# 1541-II_multi-ROM_Rev2.net
KiCad netlist of a schematic drawn in EAGLE
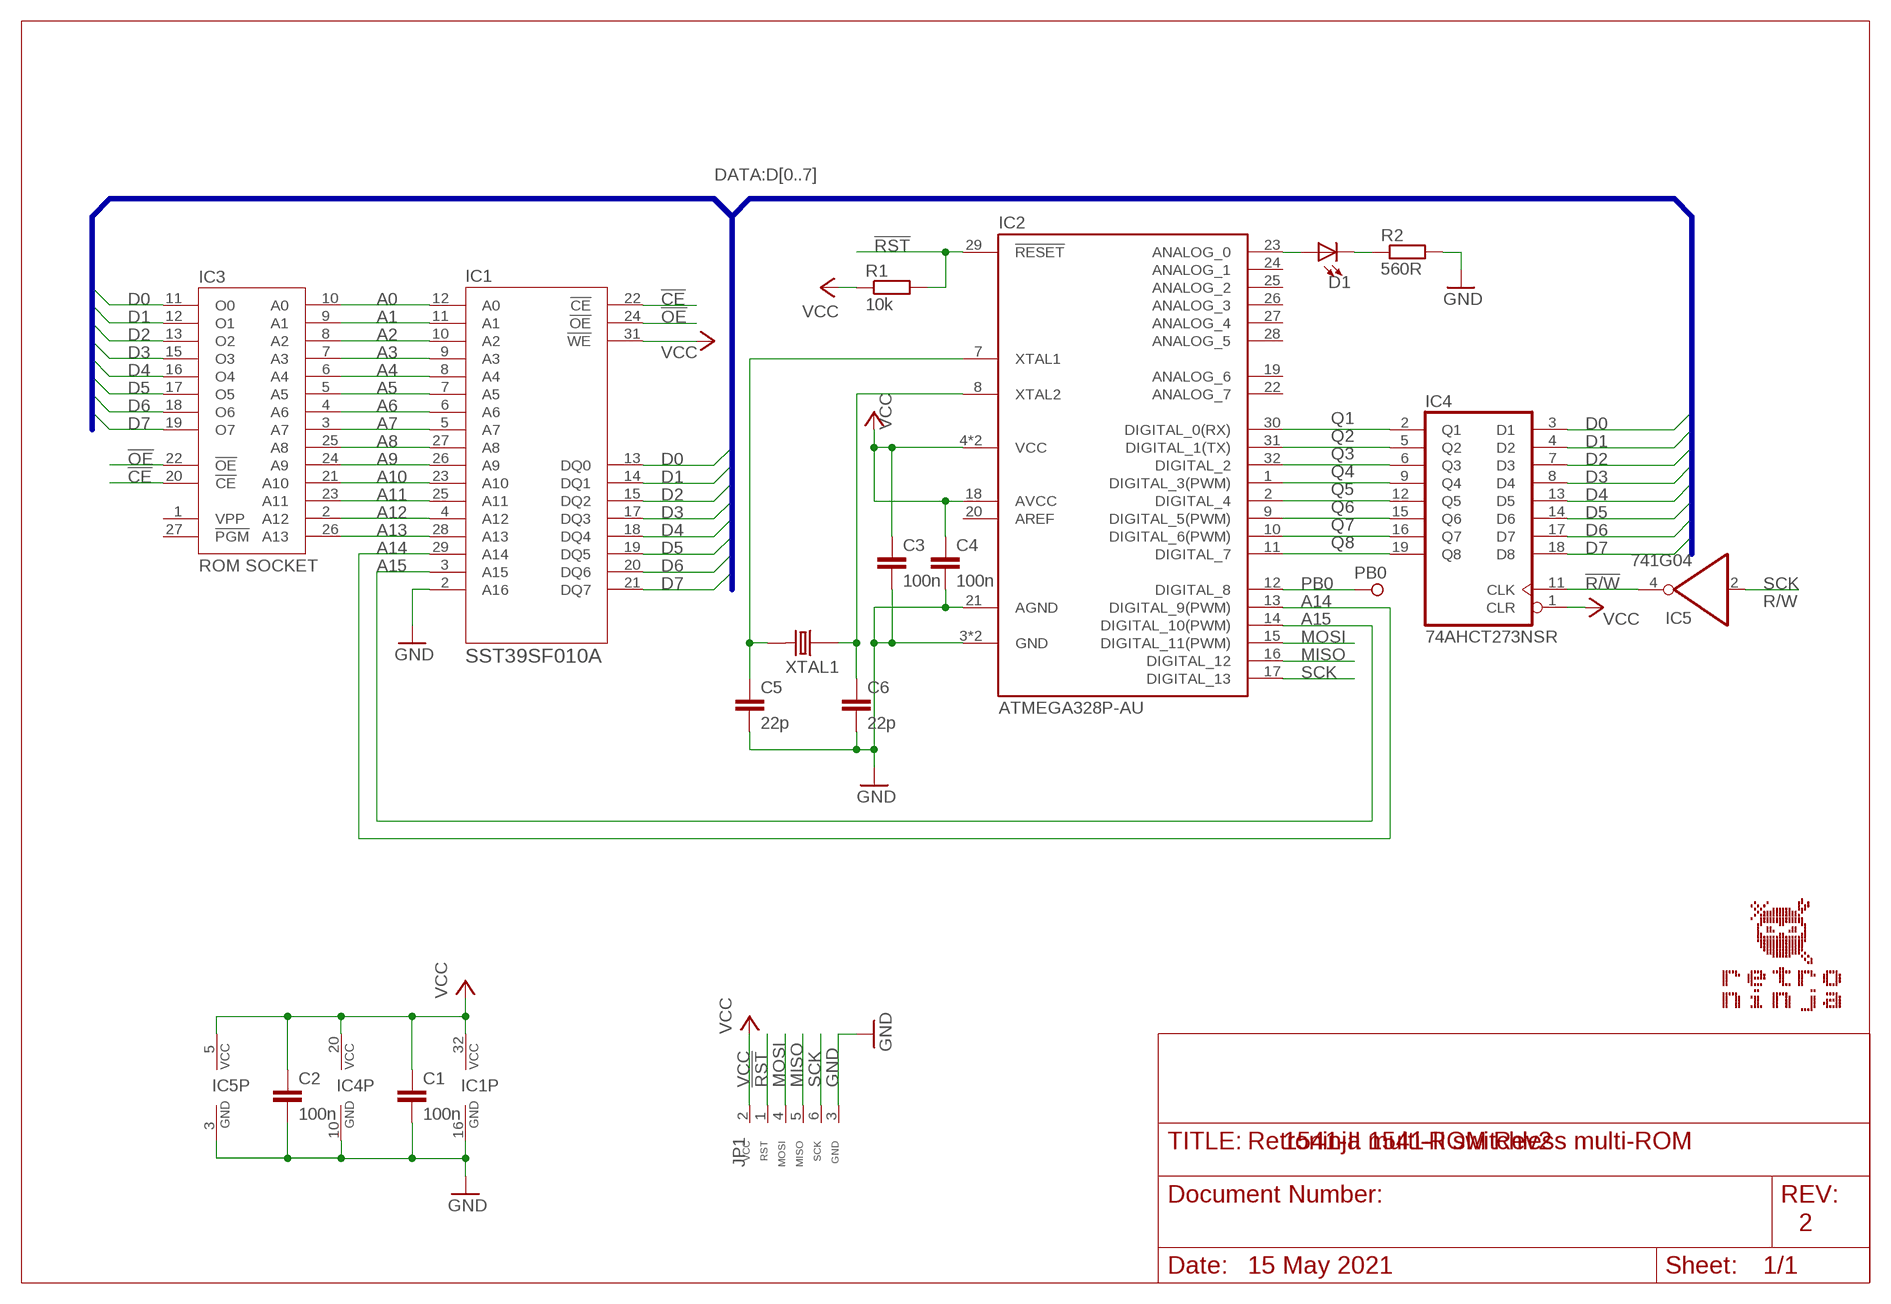
[diagram p0: schematic, sheet 1]

(export (version "E")
  (design (tool "Eeschema 10.0.6"))
  (components
    (comp (ref "C1")
      (value "100n")
      (footprint "eagle-import:C0805")
      (libsource (lib "eagle-import") (part "C-EUC0805"))
    )
    (comp (ref "C2")
      (value "100n")
      (footprint "eagle-import:C0805")
      (libsource (lib "eagle-import") (part "C-EUC0805"))
    )
    (comp (ref "C3")
      (value "100n")
      (footprint "eagle-import:C0805")
      (libsource (lib "eagle-import") (part "C-EUC0805"))
    )
    (comp (ref "C4")
      (value "100n")
      (footprint "eagle-import:C0805")
      (libsource (lib "eagle-import") (part "C-EUC0805"))
    )
    (comp (ref "C5")
      (value "22p")
      (footprint "eagle-import:C0805")
      (libsource (lib "eagle-import") (part "C-EUC0805"))
    )
    (comp (ref "C6")
      (value "22p")
      (footprint "eagle-import:C0805")
      (libsource (lib "eagle-import") (part "C-EUC0805"))
    )
    (comp (ref "D1")
      (value "LED_1206")
      (footprint "eagle-import:LED1206")
      (libsource (lib "eagle-import") (part "LED_1206"))
    )
    (comp (ref "IC1")
      (value "SST39SF010A")
      (footprint "eagle-import:PLCC32_SHORT")
      (libsource (lib "eagle-import") (part "SST39XX010_PLCC_SHORT"))
    )
    (comp (ref "IC2")
      (value "ATMEGA328P-AU")
      (footprint "eagle-import:TQFP32")
      (libsource (lib "eagle-import") (part "ARDUINO_168_328_TQFP"))
    )
    (comp (ref "IC3")
      (value "ROM SOCKET")
      (footprint "eagle-import:DIL28-6_DOWNPINS")
      (libsource (lib "eagle-import") (part "27C128_DOWNPINS"))
    )
    (comp (ref "IC4")
      (value "74AHCT273NSR")
      (footprint "eagle-import:SO20")
      (libsource (lib "eagle-import") (part "74273NS"))
    )
    (comp (ref "IC5")
      (value "741G04")
      (footprint "eagle-import:SOT23-5")
      (libsource (lib "eagle-import") (part "741G04_SOT23"))
    )
    (comp (ref "JP1")
      (value "ICSP_CONNECTOR_TL866_RIGHT2")
      (footprint "eagle-import:HEADER_1X6_RIGHT")
      (libsource (lib "eagle-import") (part "ICSP_CONNECTOR_TL866_RIGHT2"))
    )
    (comp (ref "PB0")
      (value "TEST_POINT_TH")
      (footprint "eagle-import:TEST_POINT_TH")
      (libsource (lib "eagle-import") (part "TEST_POINT_TH"))
    )
    (comp (ref "R1")
      (value "10k")
      (footprint "eagle-import:R0805")
      (libsource (lib "eagle-import") (part "R-EU_R0805"))
    )
    (comp (ref "R2")
      (value "560R")
      (footprint "eagle-import:R0805")
      (libsource (lib "eagle-import") (part "R-EU_R0805"))
    )
    (comp (ref "XTAL1")
      (value "CRYSTAL")
      (footprint "eagle-import:CRYSTAL_SMD-2_7X4X2.3")
      (libsource (lib "eagle-import") (part "CRYSTAL"))
    )
  )
  (nets
    (net (code "9") (name "/A0") (class "Default")
      (node (ref "IC1") (pin "12") (pinfunction "A0_12") (pintype "input"))
      (node (ref "IC3") (pin "10") (pinfunction "A0_10") (pintype "input"))
    )
    (net (code "10") (name "/A1") (class "Default")
      (node (ref "IC1") (pin "11") (pinfunction "A1_11") (pintype "input"))
      (node (ref "IC3") (pin "9") (pinfunction "A1_9") (pintype "input"))
    )
    (net (code "11") (name "/A2") (class "Default")
      (node (ref "IC1") (pin "10") (pinfunction "A2_10") (pintype "input"))
      (node (ref "IC3") (pin "8") (pinfunction "A2_8") (pintype "input"))
    )
    (net (code "12") (name "/A3") (class "Default")
      (node (ref "IC1") (pin "9") (pinfunction "A3_9") (pintype "input"))
      (node (ref "IC3") (pin "7") (pinfunction "A3_7") (pintype "input"))
    )
    (net (code "13") (name "/A4") (class "Default")
      (node (ref "IC1") (pin "8") (pinfunction "A4_8") (pintype "input"))
      (node (ref "IC3") (pin "6") (pinfunction "A4_6") (pintype "input"))
    )
    (net (code "14") (name "/A5") (class "Default")
      (node (ref "IC1") (pin "7") (pinfunction "A5_7") (pintype "input"))
      (node (ref "IC3") (pin "5") (pinfunction "A5_5") (pintype "input"))
    )
    (net (code "15") (name "/A6") (class "Default")
      (node (ref "IC1") (pin "6") (pinfunction "A6_6") (pintype "input"))
      (node (ref "IC3") (pin "4") (pinfunction "A6_4") (pintype "input"))
    )
    (net (code "16") (name "/A7") (class "Default")
      (node (ref "IC1") (pin "5") (pinfunction "A7_5") (pintype "input"))
      (node (ref "IC3") (pin "3") (pinfunction "A7_3") (pintype "input"))
    )
    (net (code "17") (name "/A8") (class "Default")
      (node (ref "IC1") (pin "27") (pinfunction "A8_27") (pintype "input"))
      (node (ref "IC3") (pin "25") (pinfunction "A8_25") (pintype "input"))
    )
    (net (code "18") (name "/A9") (class "Default")
      (node (ref "IC1") (pin "26") (pinfunction "A9_26") (pintype "input"))
      (node (ref "IC3") (pin "24") (pinfunction "A9_24") (pintype "input"))
    )
    (net (code "19") (name "/A10") (class "Default")
      (node (ref "IC1") (pin "23") (pinfunction "A10_23") (pintype "input"))
      (node (ref "IC3") (pin "21") (pinfunction "A10_21") (pintype "input"))
    )
    (net (code "20") (name "/A11") (class "Default")
      (node (ref "IC1") (pin "25") (pinfunction "A11_25") (pintype "input"))
      (node (ref "IC3") (pin "23") (pinfunction "A11_23") (pintype "input"))
    )
    (net (code "21") (name "/A12") (class "Default")
      (node (ref "IC1") (pin "4") (pinfunction "A12_4") (pintype "input"))
      (node (ref "IC3") (pin "2") (pinfunction "A12_2") (pintype "input"))
    )
    (net (code "22") (name "/A13") (class "Default")
      (node (ref "IC1") (pin "28") (pinfunction "A13_28") (pintype "input"))
      (node (ref "IC3") (pin "26") (pinfunction "A13_26") (pintype "input"))
    )
    (net (code "23") (name "/A14") (class "Default")
      (node (ref "IC1") (pin "29") (pinfunction "A14_29") (pintype "input"))
      (node (ref "IC2") (pin "13") (pinfunction "DIGITAL_9(PWM)_13") (pintype "bidirectional"))
    )
    (net (code "24") (name "/A15") (class "Default")
      (node (ref "IC1") (pin "3") (pinfunction "A15_3") (pintype "input"))
      (node (ref "IC2") (pin "14") (pinfunction "DIGITAL_10(PWM)_14") (pintype "bidirectional"))
    )
    (net (code "25") (name "/D0") (class "Default")
      (node (ref "IC1") (pin "13") (pinfunction "DQ0_13") (pintype "bidirectional"))
      (node (ref "IC3") (pin "11") (pinfunction "O0_11") (pintype "tri_state"))
      (node (ref "IC4") (pin "3") (pinfunction "D1_3") (pintype "input"))
    )
    (net (code "26") (name "/D1") (class "Default")
      (node (ref "IC1") (pin "14") (pinfunction "DQ1_14") (pintype "bidirectional"))
      (node (ref "IC3") (pin "12") (pinfunction "O1_12") (pintype "tri_state"))
      (node (ref "IC4") (pin "4") (pinfunction "D2_4") (pintype "input"))
    )
    (net (code "27") (name "/D2") (class "Default")
      (node (ref "IC1") (pin "15") (pinfunction "DQ2_15") (pintype "bidirectional"))
      (node (ref "IC3") (pin "13") (pinfunction "O2_13") (pintype "tri_state"))
      (node (ref "IC4") (pin "7") (pinfunction "D3_7") (pintype "input"))
    )
    (net (code "28") (name "/D3") (class "Default")
      (node (ref "IC1") (pin "17") (pinfunction "DQ3_17") (pintype "bidirectional"))
      (node (ref "IC3") (pin "15") (pinfunction "O3_15") (pintype "tri_state"))
      (node (ref "IC4") (pin "8") (pinfunction "D4_8") (pintype "input"))
    )
    (net (code "29") (name "/D4") (class "Default")
      (node (ref "IC1") (pin "18") (pinfunction "DQ4_18") (pintype "bidirectional"))
      (node (ref "IC3") (pin "16") (pinfunction "O4_16") (pintype "tri_state"))
      (node (ref "IC4") (pin "13") (pinfunction "D5_13") (pintype "input"))
    )
    (net (code "30") (name "/D5") (class "Default")
      (node (ref "IC1") (pin "19") (pinfunction "DQ5_19") (pintype "bidirectional"))
      (node (ref "IC3") (pin "17") (pinfunction "O5_17") (pintype "tri_state"))
      (node (ref "IC4") (pin "14") (pinfunction "D6_14") (pintype "input"))
    )
    (net (code "31") (name "/D6") (class "Default")
      (node (ref "IC1") (pin "20") (pinfunction "DQ6_20") (pintype "bidirectional"))
      (node (ref "IC3") (pin "18") (pinfunction "O6_18") (pintype "tri_state"))
      (node (ref "IC4") (pin "17") (pinfunction "D7_17") (pintype "input"))
    )
    (net (code "32") (name "/D7") (class "Default")
      (node (ref "IC1") (pin "21") (pinfunction "DQ7_21") (pintype "bidirectional"))
      (node (ref "IC3") (pin "19") (pinfunction "O7_19") (pintype "tri_state"))
      (node (ref "IC4") (pin "18") (pinfunction "D8_18") (pintype "input"))
    )
    (net (code "34") (name "/MISO") (class "Default")
      (node (ref "IC2") (pin "16") (pinfunction "DIGITAL_12_16") (pintype "bidirectional"))
      (node (ref "JP1") (pin "5") (pinfunction "MISO_5") (pintype "output"))
    )
    (net (code "35") (name "/MOSI") (class "Default")
      (node (ref "IC2") (pin "15") (pinfunction "DIGITAL_11(PWM)_15") (pintype "bidirectional"))
      (node (ref "JP1") (pin "4") (pinfunction "MOSI_4") (pintype "input"))
    )
    (net (code "36") (name "/PB0") (class "Default")
      (node (ref "IC2") (pin "12") (pinfunction "DIGITAL_8_12") (pintype "bidirectional"))
      (node (ref "PB0") (pin "P$1") (pinfunction "TP_P$1") (pintype "passive"))
    )
    (net (code "37") (name "/Q1") (class "Default")
      (node (ref "IC2") (pin "30") (pinfunction "DIGITAL_0(RX)_30") (pintype "bidirectional"))
      (node (ref "IC4") (pin "2") (pinfunction "Q1_2") (pintype "output"))
    )
    (net (code "38") (name "/Q2") (class "Default")
      (node (ref "IC2") (pin "31") (pinfunction "DIGITAL_1(TX)_31") (pintype "bidirectional"))
      (node (ref "IC4") (pin "5") (pinfunction "Q2_5") (pintype "output"))
    )
    (net (code "39") (name "/Q3") (class "Default")
      (node (ref "IC2") (pin "32") (pinfunction "DIGITAL_2_32") (pintype "bidirectional"))
      (node (ref "IC4") (pin "6") (pinfunction "Q3_6") (pintype "output"))
    )
    (net (code "40") (name "/Q4") (class "Default")
      (node (ref "IC2") (pin "1") (pinfunction "DIGITAL_3(PWM)_1") (pintype "bidirectional"))
      (node (ref "IC4") (pin "9") (pinfunction "Q4_9") (pintype "output"))
    )
    (net (code "41") (name "/Q5") (class "Default")
      (node (ref "IC2") (pin "2") (pinfunction "DIGITAL_4_2") (pintype "bidirectional"))
      (node (ref "IC4") (pin "12") (pinfunction "Q5_12") (pintype "output"))
    )
    (net (code "42") (name "/Q6") (class "Default")
      (node (ref "IC2") (pin "9") (pinfunction "DIGITAL_5(PWM)_9") (pintype "bidirectional"))
      (node (ref "IC4") (pin "15") (pinfunction "Q6_15") (pintype "output"))
    )
    (net (code "43") (name "/Q7") (class "Default")
      (node (ref "IC2") (pin "10") (pinfunction "DIGITAL_6(PWM)_10") (pintype "bidirectional"))
      (node (ref "IC4") (pin "16") (pinfunction "Q7_16") (pintype "output"))
    )
    (net (code "44") (name "/Q8") (class "Default")
      (node (ref "IC2") (pin "11") (pinfunction "DIGITAL_7_11") (pintype "bidirectional"))
      (node (ref "IC4") (pin "19") (pinfunction "Q8_19") (pintype "output"))
    )
    (net (code "45") (name "/SCK") (class "Default")
      (node (ref "IC2") (pin "17") (pinfunction "DIGITAL_13_17") (pintype "bidirectional"))
      (node (ref "IC5") (pin "2") (pinfunction "I_2") (pintype "input"))
      (node (ref "JP1") (pin "6") (pinfunction "SCK_6") (pintype "input"))
    )
    (net (code "46") (name "/~{CE}") (class "Default")
      (node (ref "IC1") (pin "22") (pinfunction "~{CE}_22") (pintype "input"))
      (node (ref "IC3") (pin "20") (pinfunction "~{CE}_20") (pintype "input"))
    )
    (net (code "47") (name "/~{OE}") (class "Default")
      (node (ref "IC1") (pin "24") (pinfunction "~{OE}_24") (pintype "input"))
      (node (ref "IC3") (pin "22") (pinfunction "~{OE}_22") (pintype "input"))
    )
    (net (code "48") (name "/~{RST}") (class "Default")
      (node (ref "IC2") (pin "29") (pinfunction "~{RESET}_29") (pintype "bidirectional"))
      (node (ref "JP1") (pin "1") (pinfunction "RST_1") (pintype "input"))
      (node (ref "R1") (pin "2") (pinfunction "2_2") (pintype "passive"))
    )
    (net (code "49") (name "/~{R{slash}W}") (class "Default")
      (node (ref "IC4") (pin "11") (pinfunction "CLK_11") (pintype "input"))
      (node (ref "IC5") (pin "4") (pinfunction "O_4") (pintype "output"))
    )
    (net (code "50") (name "GND") (class "Default")
      (node (ref "C1") (pin "2") (pinfunction "2_2") (pintype "passive"))
      (node (ref "C2") (pin "2") (pinfunction "2_2") (pintype "passive"))
      (node (ref "C3") (pin "2") (pinfunction "2_2") (pintype "passive"))
      (node (ref "C4") (pin "2") (pinfunction "2_2") (pintype "passive"))
      (node (ref "C5") (pin "2") (pinfunction "2_2") (pintype "passive"))
      (node (ref "C6") (pin "2") (pinfunction "2_2") (pintype "passive"))
      (node (ref "IC1") (pin "16") (pinfunction "GND_16") (pintype "power_in"))
      (node (ref "IC1") (pin "2") (pinfunction "A16_2") (pintype "input"))
      (node (ref "IC2") (pin "21") (pinfunction "AGND_21") (pintype "passive"))
      (node (ref "IC2") (pin "3") (pinfunction "GND_3") (pintype "passive"))
      (node (ref "IC2") (pin "5") (pinfunction "GND_5") (pintype "passive"))
      (node (ref "IC4") (pin "10") (pinfunction "GND_10") (pintype "power_in"))
      (node (ref "IC5") (pin "3") (pinfunction "GND_3") (pintype "power_in"))
      (node (ref "JP1") (pin "3") (pinfunction "GND_3") (pintype "power_in"))
      (node (ref "R2") (pin "2") (pinfunction "2_2") (pintype "passive"))
    )
    (net (code "51") (name "Net-(D1-PadC)") (class "Default")
      (node (ref "D1") (pin "C") (pinfunction "C_C") (pintype "passive"))
      (node (ref "R2") (pin "1") (pinfunction "1_1") (pintype "passive"))
    )
    (net (code "52") (name "Net-(IC2-ANALOG_0)") (class "Default")
      (node (ref "D1") (pin "A") (pinfunction "A_A") (pintype "passive"))
      (node (ref "IC2") (pin "23") (pinfunction "ANALOG_0_23") (pintype "bidirectional"))
    )
    (net (code "53") (name "Net-(IC2-XTAL1)") (class "Default")
      (node (ref "C5") (pin "1") (pinfunction "1_1") (pintype "passive"))
      (node (ref "IC2") (pin "7") (pinfunction "XTAL1_7") (pintype "bidirectional"))
      (node (ref "XTAL1") (pin "2") (pinfunction "2_2") (pintype "passive"))
    )
    (net (code "54") (name "Net-(IC2-XTAL2)") (class "Default")
      (node (ref "C6") (pin "1") (pinfunction "1_1") (pintype "passive"))
      (node (ref "IC2") (pin "8") (pinfunction "XTAL2_8") (pintype "bidirectional"))
      (node (ref "XTAL1") (pin "1") (pinfunction "1_1") (pintype "passive"))
    )
    (net (code "55") (name "VCC") (class "Default")
      (node (ref "C1") (pin "1") (pinfunction "1_1") (pintype "passive"))
      (node (ref "C2") (pin "1") (pinfunction "1_1") (pintype "passive"))
      (node (ref "C3") (pin "1") (pinfunction "1_1") (pintype "passive"))
      (node (ref "C4") (pin "1") (pinfunction "1_1") (pintype "passive"))
      (node (ref "IC1") (pin "31") (pinfunction "~{WE}_31") (pintype "input"))
      (node (ref "IC1") (pin "32") (pinfunction "VCC_32") (pintype "power_in"))
      (node (ref "IC2") (pin "18") (pinfunction "AVCC_18") (pintype "passive"))
      (node (ref "IC2") (pin "4") (pinfunction "VCC_4") (pintype "passive"))
      (node (ref "IC2") (pin "6") (pinfunction "VCC_6") (pintype "passive"))
      (node (ref "IC4") (pin "1") (pinfunction "CLR_1") (pintype "input"))
      (node (ref "IC4") (pin "20") (pinfunction "VCC_20") (pintype "power_in"))
      (node (ref "IC5") (pin "5") (pinfunction "VCC_5") (pintype "power_in"))
      (node (ref "JP1") (pin "2") (pinfunction "VCC_2") (pintype "power_in"))
      (node (ref "R1") (pin "1") (pinfunction "1_1") (pintype "passive"))
    )
    (net (code "56") (name "unconnected-(IC2-ANALOG_1-Pad24)") (class "Default")
      (node (ref "IC2") (pin "24") (pinfunction "ANALOG_1_24") (pintype "bidirectional"))
    )
    (net (code "57") (name "unconnected-(IC2-ANALOG_2-Pad25)") (class "Default")
      (node (ref "IC2") (pin "25") (pinfunction "ANALOG_2_25") (pintype "bidirectional"))
    )
    (net (code "58") (name "unconnected-(IC2-ANALOG_3-Pad26)") (class "Default")
      (node (ref "IC2") (pin "26") (pinfunction "ANALOG_3_26") (pintype "bidirectional"))
    )
    (net (code "59") (name "unconnected-(IC2-ANALOG_4-Pad27)") (class "Default")
      (node (ref "IC2") (pin "27") (pinfunction "ANALOG_4_27") (pintype "bidirectional"))
    )
    (net (code "60") (name "unconnected-(IC2-ANALOG_5-Pad28)") (class "Default")
      (node (ref "IC2") (pin "28") (pinfunction "ANALOG_5_28") (pintype "bidirectional"))
    )
    (net (code "61") (name "unconnected-(IC2-ANALOG_6-Pad19)") (class "Default")
      (node (ref "IC2") (pin "19") (pinfunction "ANALOG_6_19") (pintype "bidirectional"))
    )
    (net (code "62") (name "unconnected-(IC2-ANALOG_7-Pad22)") (class "Default")
      (node (ref "IC2") (pin "22") (pinfunction "ANALOG_7_22") (pintype "bidirectional"))
    )
    (net (code "63") (name "unconnected-(IC2-AREF-Pad20)") (class "Default")
      (node (ref "IC2") (pin "20") (pinfunction "AREF_20") (pintype "passive"))
    )
    (net (code "64") (name "unconnected-(IC3A-VPP-Pad1)") (class "Default")
      (node (ref "IC3") (pin "1") (pinfunction "VPP_1") (pintype "input"))
    )
    (net (code "65") (name "unconnected-(IC3A-~{PGM}-Pad27)") (class "Default")
      (node (ref "IC3") (pin "27") (pinfunction "~{PGM}_27") (pintype "input"))
    )
  )
)
